# battery_protect.net
KiCad netlist of a schematic drawn in Altium Designer
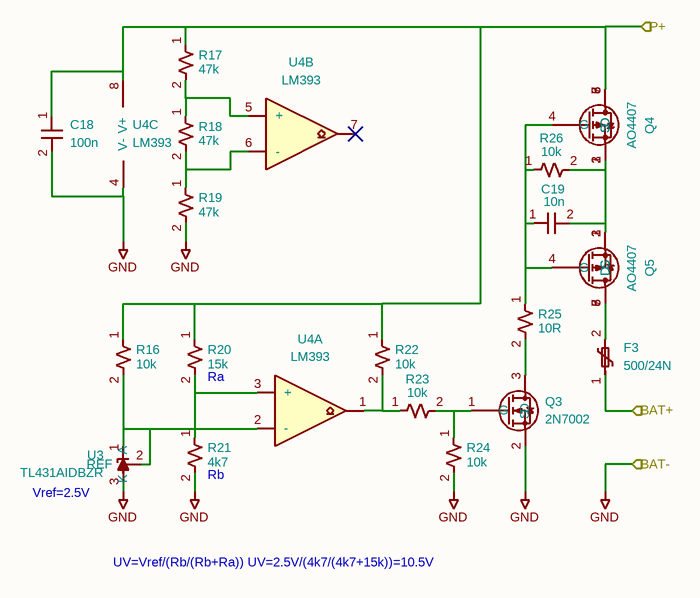
[diagram p0: battery_protect.SchDoc]

(export (version "E")
  (design (tool "Eeschema 10.0.6"))
  (components
    (comp (ref "C18")
      (value "100n")
      (description "Unpolarized capacitor, small symbol")
      (libsource (lib "Device") (part "C_Small"))
    )
    (comp (ref "C19")
      (value "10n")
      (description "Unpolarized capacitor, small symbol")
      (libsource (lib "Device") (part "C_Small"))
    )
    (comp (ref "F3")
      (value "500/24N")
      (description "24V 5A 40A 10A 2920 Resettable Fuses ROHS")
      (libsource (lib "Device") (part "Polyfuse_Small"))
    )
    (comp (ref "Q3")
      (value "2N7002")
      (description "0.115A Id, 60V Vds, N-Channel MOSFET, SOT-23")
      (libsource (lib "Transistor_FET") (part "2N7002"))
    )
    (comp (ref "Q4")
      (value "AO4407")
      (description "-6.7A Id, -20V Vds, P-Channel HEXFET Power MOSFET, SO-8")
      (libsource (lib "Transistor_FET") (part "IRF7404"))
    )
    (comp (ref "Q5")
      (value "AO4407")
      (description "-6.7A Id, -20V Vds, P-Channel HEXFET Power MOSFET, SO-8")
      (libsource (lib "Transistor_FET") (part "IRF7404"))
    )
    (comp (ref "R16")
      (value "10k")
      (description "Resistor, small US symbol")
      (libsource (lib "Device") (part "R_Small_US"))
    )
    (comp (ref "R17")
      (value "47k")
      (description "Resistor, small US symbol")
      (libsource (lib "Device") (part "R_Small_US"))
    )
    (comp (ref "R18")
      (value "47k")
      (description "Resistor, small US symbol")
      (libsource (lib "Device") (part "R_Small_US"))
    )
    (comp (ref "R19")
      (value "47k")
      (description "Resistor, small US symbol")
      (libsource (lib "Device") (part "R_Small_US"))
    )
    (comp (ref "R20")
      (value "15k")
      (description "Resistor, small US symbol")
      (libsource (lib "Device") (part "R_Small_US"))
    )
    (comp (ref "R21")
      (value "4k7")
      (description "Resistor, small US symbol")
      (libsource (lib "Device") (part "R_Small_US"))
    )
    (comp (ref "R22")
      (value "10k")
      (description "Resistor, small US symbol")
      (libsource (lib "Device") (part "R_Small_US"))
    )
    (comp (ref "R23")
      (value "10k")
      (description "Resistor, small US symbol")
      (libsource (lib "Device") (part "R_Small_US"))
    )
    (comp (ref "R24")
      (value "10k")
      (description "Resistor, small US symbol")
      (libsource (lib "Device") (part "R_Small_US"))
    )
    (comp (ref "R25")
      (value "10R")
      (description "Resistor, small US symbol")
      (libsource (lib "Device") (part "R_Small_US"))
    )
    (comp (ref "R26")
      (value "10k")
      (description "Resistor, small US symbol")
      (libsource (lib "Device") (part "R_Small_US"))
    )
    (comp (ref "U3")
      (value "TL431AIDBZR")
      (description "Shunt Regulator, SOT-23")
      (libsource (lib "Reference_Voltage") (part "TL431DBZ"))
    )
    (comp (ref "U4")
      (value "LM393")
      (description "Low-Power, Low-Offset Voltage, Dual Comparators, DIP-8/SOIC-8/TO-99-8")
      (libsource (lib "Comparator") (part "LM393"))
    )
  )
  (nets
    (net (code "1") (name "/BAT+") (class "Default")
      (node (ref "F3") (pin "1") (pinfunction "1_1") (pintype "passive"))
    )
    (net (code "2") (name "/P+") (class "Default")
      (node (ref "C18") (pin "1") (pinfunction "1_1") (pintype "passive"))
      (node (ref "Q4") (pin "5") (pinfunction "D_5") (pintype "passive"))
      (node (ref "Q4") (pin "6") (pinfunction "D_6") (pintype "passive"))
      (node (ref "Q4") (pin "7") (pinfunction "D_7") (pintype "passive"))
      (node (ref "Q4") (pin "8") (pinfunction "D_8") (pintype "passive"))
      (node (ref "R16") (pin "1") (pinfunction "1_1") (pintype "passive"))
      (node (ref "R17") (pin "1") (pinfunction "1_1") (pintype "passive"))
      (node (ref "R20") (pin "1") (pinfunction "1_1") (pintype "passive"))
      (node (ref "R22") (pin "1") (pinfunction "1_1") (pintype "passive"))
      (node (ref "U4") (pin "8") (pinfunction "V+_8") (pintype "passive"))
    )
    (net (code "3") (name "GND") (class "Default")
      (node (ref "C18") (pin "2") (pinfunction "2_2") (pintype "passive"))
      (node (ref "Q3") (pin "2") (pinfunction "S_2") (pintype "passive"))
      (node (ref "R19") (pin "2") (pinfunction "2_2") (pintype "passive"))
      (node (ref "R21") (pin "2") (pinfunction "2_2") (pintype "passive"))
      (node (ref "R24") (pin "2") (pinfunction "2_2") (pintype "passive"))
      (node (ref "U3") (pin "3") (pinfunction "A_3") (pintype "passive"))
      (node (ref "U4") (pin "4") (pinfunction "V-_4") (pintype "passive"))
    )
    (net (code "4") (name "Net-(C19-Pad2)") (class "Default")
      (node (ref "C19") (pin "2") (pinfunction "2_2") (pintype "passive"))
      (node (ref "Q4") (pin "1") (pinfunction "S_1") (pintype "passive"))
      (node (ref "Q4") (pin "2") (pinfunction "S_2") (pintype "passive"))
      (node (ref "Q4") (pin "3") (pinfunction "S_3") (pintype "passive"))
      (node (ref "Q5") (pin "1") (pinfunction "S_1") (pintype "passive"))
      (node (ref "Q5") (pin "2") (pinfunction "S_2") (pintype "passive"))
      (node (ref "Q5") (pin "3") (pinfunction "S_3") (pintype "passive"))
      (node (ref "R26") (pin "2") (pinfunction "2_2") (pintype "passive"))
    )
    (net (code "5") (name "Net-(F3-Pad2)") (class "Default")
      (node (ref "F3") (pin "2") (pinfunction "2_2") (pintype "passive"))
      (node (ref "Q5") (pin "5") (pinfunction "D_5") (pintype "passive"))
      (node (ref "Q5") (pin "6") (pinfunction "D_6") (pintype "passive"))
      (node (ref "Q5") (pin "7") (pinfunction "D_7") (pintype "passive"))
      (node (ref "Q5") (pin "8") (pinfunction "D_8") (pintype "passive"))
    )
    (net (code "6") (name "Net-(Q3-D)") (class "Default")
      (node (ref "Q3") (pin "3") (pinfunction "D_3") (pintype "passive"))
      (node (ref "R25") (pin "2") (pinfunction "2_2") (pintype "passive"))
    )
    (net (code "7") (name "Net-(Q3-G)") (class "Default")
      (node (ref "Q3") (pin "1") (pinfunction "G_1") (pintype "passive"))
      (node (ref "R23") (pin "2") (pinfunction "2_2") (pintype "passive"))
      (node (ref "R24") (pin "1") (pinfunction "1_1") (pintype "passive"))
    )
    (net (code "8") (name "Net-(Q4-G)") (class "Default")
      (node (ref "C19") (pin "1") (pinfunction "1_1") (pintype "passive"))
      (node (ref "Q4") (pin "4") (pinfunction "G_4") (pintype "passive"))
      (node (ref "Q5") (pin "4") (pinfunction "G_4") (pintype "passive"))
      (node (ref "R25") (pin "1") (pinfunction "1_1") (pintype "passive"))
      (node (ref "R26") (pin "1") (pinfunction "1_1") (pintype "passive"))
    )
    (net (code "9") (name "Net-(R22-Pad2)") (class "Default")
      (node (ref "R22") (pin "2") (pinfunction "2_2") (pintype "passive"))
      (node (ref "R23") (pin "1") (pinfunction "1_1") (pintype "passive"))
      (node (ref "U4") (pin "1") (pinfunction "1_1") (pintype "passive"))
    )
    (net (code "10") (name "Net-(U3-K)") (class "Default")
      (node (ref "R16") (pin "2") (pinfunction "2_2") (pintype "passive"))
      (node (ref "U3") (pin "1") (pinfunction "K_1") (pintype "passive"))
      (node (ref "U3") (pin "2") (pinfunction "REF_2") (pintype "passive"))
      (node (ref "U4") (pin "2") (pinfunction "-_2") (pintype "passive"))
    )
    (net (code "11") (name "Net-(U4A-+)") (class "Default")
      (node (ref "R20") (pin "2") (pinfunction "2_2") (pintype "passive"))
      (node (ref "R21") (pin "1") (pinfunction "1_1") (pintype "passive"))
      (node (ref "U4") (pin "3") (pinfunction "+_3") (pintype "passive"))
    )
    (net (code "12") (name "Net-(U4B-+)") (class "Default")
      (node (ref "R17") (pin "2") (pinfunction "2_2") (pintype "passive"))
      (node (ref "R18") (pin "1") (pinfunction "1_1") (pintype "passive"))
      (node (ref "U4") (pin "5") (pinfunction "+_5") (pintype "passive"))
    )
    (net (code "13") (name "Net-(U4B--)") (class "Default")
      (node (ref "R18") (pin "2") (pinfunction "2_2") (pintype "passive"))
      (node (ref "R19") (pin "1") (pinfunction "1_1") (pintype "passive"))
      (node (ref "U4") (pin "6") (pinfunction "-_6") (pintype "passive"))
    )
    (net (code "14") (name "unconnected-(U4-Pad7)") (class "Default")
      (node (ref "U4") (pin "7") (pinfunction "7_7") (pintype "passive+no_connect"))
    )
  )
)
